# time-led-r1.net
KiCad netlist of a schematic drawn in EAGLE
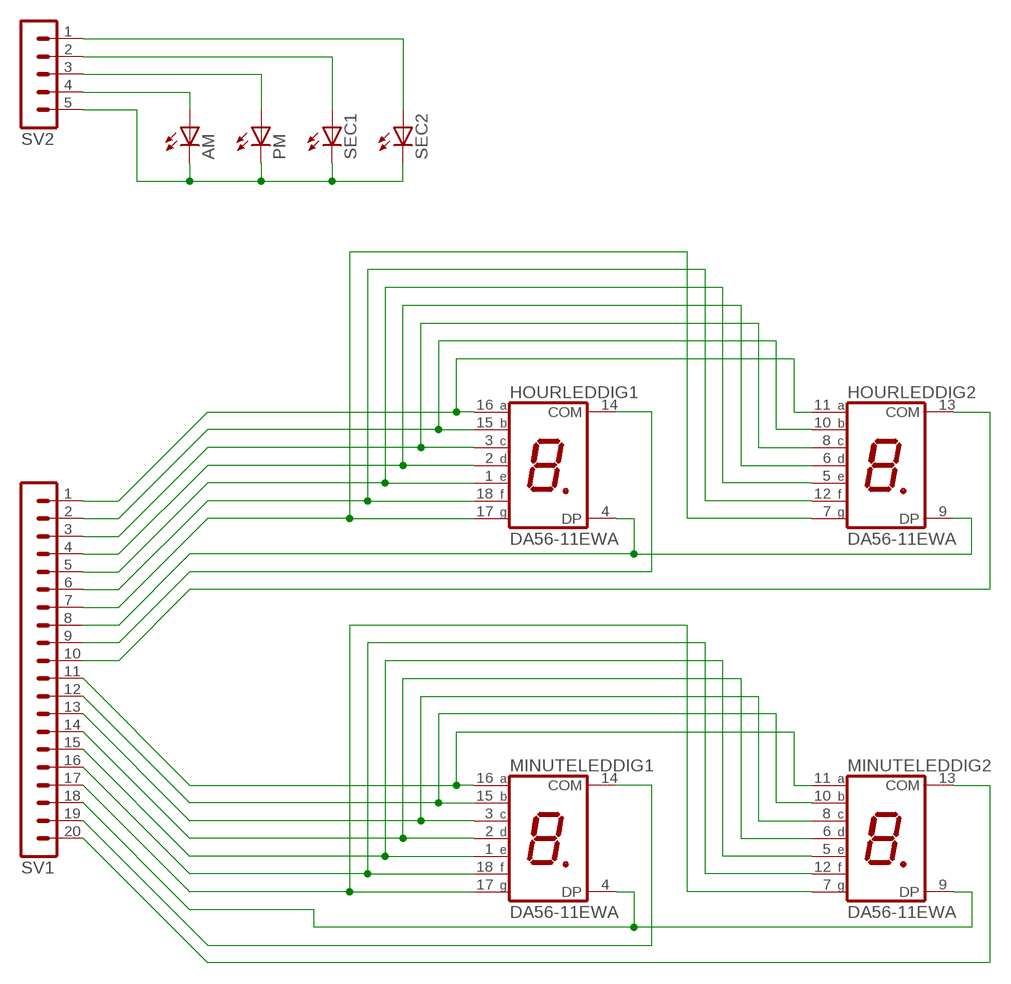
[diagram p0: schematic, sheet 1]

(export (version "E")
  (design (tool "Eeschema 10.0.6"))
  (components
    (comp (ref "AM")
      (value "LED3MM")
      (footprint "eagle-import:LED3MM")
      (libsource (lib "eagle-import") (part "LED3MM"))
    )
    (comp (ref "HOURLED")
      (value "DA56-11EWA")
      (footprint "eagle-import:DA56")
      (libsource (lib "eagle-import") (part "DA56-11EWA"))
    )
    (comp (ref "MINUTELED")
      (value "DA56-11EWA")
      (footprint "eagle-import:DA56")
      (libsource (lib "eagle-import") (part "DA56-11EWA"))
    )
    (comp (ref "PM")
      (value "LED3MM")
      (footprint "eagle-import:LED3MM")
      (libsource (lib "eagle-import") (part "LED3MM"))
    )
    (comp (ref "SEC1")
      (value "LED3MM")
      (footprint "eagle-import:LED3MM")
      (libsource (lib "eagle-import") (part "LED3MM"))
    )
    (comp (ref "SEC2")
      (value "LED3MM")
      (footprint "eagle-import:LED3MM")
      (libsource (lib "eagle-import") (part "LED3MM"))
    )
    (comp (ref "SV1")
      (value "MA20-1W")
      (footprint "eagle-import:MA20-1W")
      (libsource (lib "eagle-import") (part "MA20-1W"))
    )
    (comp (ref "SV2")
      (value "MA05-1")
      (footprint "eagle-import:MA05-1")
      (libsource (lib "eagle-import") (part "MA05-1"))
    )
  )
  (nets
    (net (code "1") (name "Net-(AM-C)") (class "Default")
      (node (ref "AM") (pin "K") (pinfunction "C_K") (pintype "passive"))
      (node (ref "PM") (pin "K") (pinfunction "C_K") (pintype "passive"))
      (node (ref "SEC1") (pin "K") (pinfunction "C_K") (pintype "passive"))
      (node (ref "SEC2") (pin "K") (pinfunction "C_K") (pintype "passive"))
      (node (ref "SV2") (pin "5") (pinfunction "5_5") (pintype "passive"))
    )
    (net (code "2") (name "Net-(AM-PadA)") (class "Default")
      (node (ref "AM") (pin "A") (pinfunction "A_A") (pintype "passive"))
      (node (ref "SV2") (pin "4") (pinfunction "4_4") (pintype "passive"))
    )
    (net (code "3") (name "Net-(HOURLEDA-A)") (class "Default")
      (node (ref "HOURLED") (pin "11") (pinfunction "A_11") (pintype "passive"))
      (node (ref "HOURLED") (pin "16") (pinfunction "A_16") (pintype "passive"))
      (node (ref "SV1") (pin "1") (pinfunction "1_1") (pintype "passive"))
    )
    (net (code "4") (name "Net-(HOURLEDA-B)") (class "Default")
      (node (ref "HOURLED") (pin "10") (pinfunction "B_10") (pintype "passive"))
      (node (ref "HOURLED") (pin "15") (pinfunction "B_15") (pintype "passive"))
      (node (ref "SV1") (pin "2") (pinfunction "2_2") (pintype "passive"))
    )
    (net (code "5") (name "Net-(HOURLEDA-C)") (class "Default")
      (node (ref "HOURLED") (pin "3") (pinfunction "C_3") (pintype "passive"))
      (node (ref "HOURLED") (pin "8") (pinfunction "C_8") (pintype "passive"))
      (node (ref "SV1") (pin "3") (pinfunction "3_3") (pintype "passive"))
    )
    (net (code "6") (name "Net-(HOURLEDA-COM)") (class "Default")
      (node (ref "HOURLED") (pin "14") (pinfunction "COM_14") (pintype "passive"))
      (node (ref "SV1") (pin "9") (pinfunction "9_9") (pintype "passive"))
    )
    (net (code "7") (name "Net-(HOURLEDA-D)") (class "Default")
      (node (ref "HOURLED") (pin "2") (pinfunction "D_2") (pintype "passive"))
      (node (ref "HOURLED") (pin "6") (pinfunction "D_6") (pintype "passive"))
      (node (ref "SV1") (pin "4") (pinfunction "4_4") (pintype "passive"))
    )
    (net (code "8") (name "Net-(HOURLEDA-DP)") (class "Default")
      (node (ref "HOURLED") (pin "4") (pinfunction "DP_4") (pintype "passive"))
      (node (ref "HOURLED") (pin "9") (pinfunction "DP_9") (pintype "passive"))
      (node (ref "SV1") (pin "8") (pinfunction "8_8") (pintype "passive"))
    )
    (net (code "9") (name "Net-(HOURLEDA-E)") (class "Default")
      (node (ref "HOURLED") (pin "1") (pinfunction "E_1") (pintype "passive"))
      (node (ref "HOURLED") (pin "5") (pinfunction "E_5") (pintype "passive"))
      (node (ref "SV1") (pin "5") (pinfunction "5_5") (pintype "passive"))
    )
    (net (code "10") (name "Net-(HOURLEDA-F)") (class "Default")
      (node (ref "HOURLED") (pin "12") (pinfunction "F_12") (pintype "passive"))
      (node (ref "HOURLED") (pin "18") (pinfunction "F_18") (pintype "passive"))
      (node (ref "SV1") (pin "6") (pinfunction "6_6") (pintype "passive"))
    )
    (net (code "11") (name "Net-(HOURLEDA-G)") (class "Default")
      (node (ref "HOURLED") (pin "17") (pinfunction "G_17") (pintype "passive"))
      (node (ref "HOURLED") (pin "7") (pinfunction "G_7") (pintype "passive"))
      (node (ref "SV1") (pin "7") (pinfunction "7_7") (pintype "passive"))
    )
    (net (code "12") (name "Net-(HOURLEDB-COM)") (class "Default")
      (node (ref "HOURLED") (pin "13") (pinfunction "COM_13") (pintype "passive"))
      (node (ref "SV1") (pin "10") (pinfunction "10_10") (pintype "passive"))
    )
    (net (code "13") (name "Net-(MINUTELEDA-A)") (class "Default")
      (node (ref "MINUTELED") (pin "11") (pinfunction "A_11") (pintype "passive"))
      (node (ref "MINUTELED") (pin "16") (pinfunction "A_16") (pintype "passive"))
      (node (ref "SV1") (pin "11") (pinfunction "11_11") (pintype "passive"))
    )
    (net (code "14") (name "Net-(MINUTELEDA-B)") (class "Default")
      (node (ref "MINUTELED") (pin "10") (pinfunction "B_10") (pintype "passive"))
      (node (ref "MINUTELED") (pin "15") (pinfunction "B_15") (pintype "passive"))
      (node (ref "SV1") (pin "12") (pinfunction "12_12") (pintype "passive"))
    )
    (net (code "15") (name "Net-(MINUTELEDA-C)") (class "Default")
      (node (ref "MINUTELED") (pin "3") (pinfunction "C_3") (pintype "passive"))
      (node (ref "MINUTELED") (pin "8") (pinfunction "C_8") (pintype "passive"))
      (node (ref "SV1") (pin "13") (pinfunction "13_13") (pintype "passive"))
    )
    (net (code "16") (name "Net-(MINUTELEDA-COM)") (class "Default")
      (node (ref "MINUTELED") (pin "14") (pinfunction "COM_14") (pintype "passive"))
      (node (ref "SV1") (pin "19") (pinfunction "19_19") (pintype "passive"))
    )
    (net (code "17") (name "Net-(MINUTELEDA-D)") (class "Default")
      (node (ref "MINUTELED") (pin "2") (pinfunction "D_2") (pintype "passive"))
      (node (ref "MINUTELED") (pin "6") (pinfunction "D_6") (pintype "passive"))
      (node (ref "SV1") (pin "14") (pinfunction "14_14") (pintype "passive"))
    )
    (net (code "18") (name "Net-(MINUTELEDA-DP)") (class "Default")
      (node (ref "MINUTELED") (pin "4") (pinfunction "DP_4") (pintype "passive"))
      (node (ref "MINUTELED") (pin "9") (pinfunction "DP_9") (pintype "passive"))
      (node (ref "SV1") (pin "18") (pinfunction "18_18") (pintype "passive"))
    )
    (net (code "19") (name "Net-(MINUTELEDA-E)") (class "Default")
      (node (ref "MINUTELED") (pin "1") (pinfunction "E_1") (pintype "passive"))
      (node (ref "MINUTELED") (pin "5") (pinfunction "E_5") (pintype "passive"))
      (node (ref "SV1") (pin "15") (pinfunction "15_15") (pintype "passive"))
    )
    (net (code "20") (name "Net-(MINUTELEDA-F)") (class "Default")
      (node (ref "MINUTELED") (pin "12") (pinfunction "F_12") (pintype "passive"))
      (node (ref "MINUTELED") (pin "18") (pinfunction "F_18") (pintype "passive"))
      (node (ref "SV1") (pin "16") (pinfunction "16_16") (pintype "passive"))
    )
    (net (code "21") (name "Net-(MINUTELEDA-G)") (class "Default")
      (node (ref "MINUTELED") (pin "17") (pinfunction "G_17") (pintype "passive"))
      (node (ref "MINUTELED") (pin "7") (pinfunction "G_7") (pintype "passive"))
      (node (ref "SV1") (pin "17") (pinfunction "17_17") (pintype "passive"))
    )
    (net (code "22") (name "Net-(MINUTELEDB-COM)") (class "Default")
      (node (ref "MINUTELED") (pin "13") (pinfunction "COM_13") (pintype "passive"))
      (node (ref "SV1") (pin "20") (pinfunction "20_20") (pintype "passive"))
    )
    (net (code "23") (name "Net-(PM-PadA)") (class "Default")
      (node (ref "PM") (pin "A") (pinfunction "A_A") (pintype "passive"))
      (node (ref "SV2") (pin "3") (pinfunction "3_3") (pintype "passive"))
    )
    (net (code "24") (name "Net-(SEC1-PadA)") (class "Default")
      (node (ref "SEC1") (pin "A") (pinfunction "A_A") (pintype "passive"))
      (node (ref "SV2") (pin "2") (pinfunction "2_2") (pintype "passive"))
    )
    (net (code "25") (name "Net-(SEC2-PadA)") (class "Default")
      (node (ref "SEC2") (pin "A") (pinfunction "A_A") (pintype "passive"))
      (node (ref "SV2") (pin "1") (pinfunction "1_1") (pintype "passive"))
    )
  )
)
